# Adafruit_2_0_inch_240x320_IPS_TFT.net
KiCad netlist of a schematic drawn in EAGLE
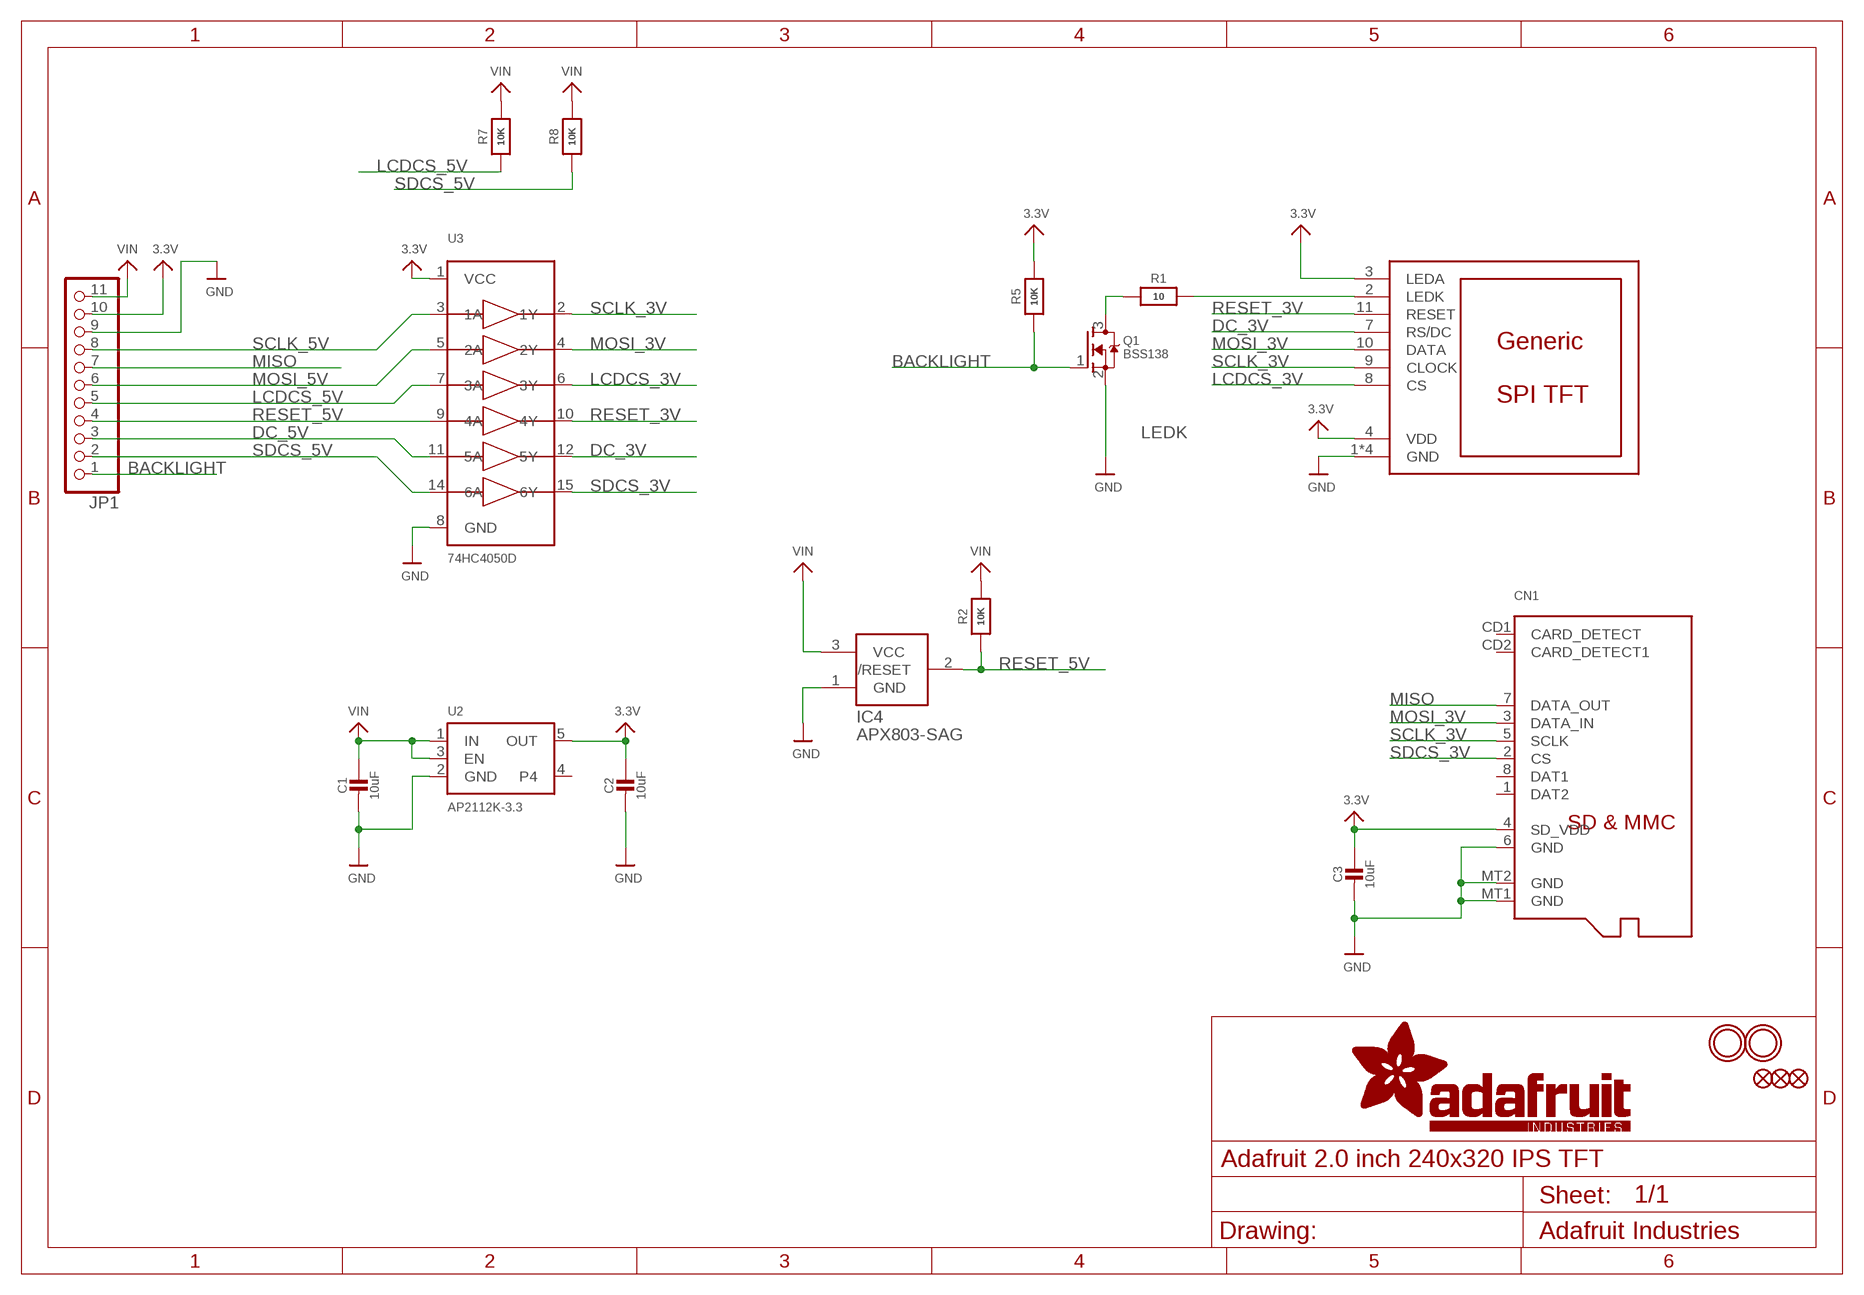
[diagram p0: schematic, sheet 1]

(export (version "E")
  (design (tool "Eeschema 10.0.6"))
  (components
    (comp (ref "C1")
      (value "10uF")
      (footprint "eagle-import:0805-NO")
      (libsource (lib "eagle-import") (part "CAP_CERAMIC0805-NOOUTLINE"))
    )
    (comp (ref "C2")
      (value "10uF")
      (footprint "eagle-import:0805-NO")
      (libsource (lib "eagle-import") (part "CAP_CERAMIC0805-NOOUTLINE"))
    )
    (comp (ref "C3")
      (value "10uF")
      (footprint "eagle-import:0805-NO")
      (libsource (lib "eagle-import") (part "CAP_CERAMIC0805-NOOUTLINE"))
    )
    (comp (ref "CN1")
      (value "MICROSD")
      (footprint "eagle-import:MICROSD")
      (libsource (lib "eagle-import") (part "MICROSD"))
    )
    (comp (ref "DISP1")
      (value "DISP_LCD_GENERIC_SPI_2.0IN_240X320")
      (footprint "eagle-import:TFT_2.0IN_240X320_12P")
      (libsource (lib "eagle-import") (part "DISP_LCD_GENERIC_SPI_2.0IN_240X320"))
    )
    (comp (ref "FID1")
      (value "FIDUCIAL_1MM")
      (footprint "eagle-import:FIDUCIAL_1MM")
      (libsource (lib "eagle-import") (part "FIDUCIAL_1MM"))
    )
    (comp (ref "FID2")
      (value "FIDUCIAL_1MM")
      (footprint "eagle-import:FIDUCIAL_1MM")
      (libsource (lib "eagle-import") (part "FIDUCIAL_1MM"))
    )
    (comp (ref "FID3")
      (value "FIDUCIAL_1MM")
      (footprint "eagle-import:FIDUCIAL_1MM")
      (fields (field (name "BOM") "EXCLUDE"))
      (libsource (lib "eagle-import") (part "FIDUCIAL_1MM"))
    )
    (comp (ref "IC4")
      (value "APX803-SAG")
      (footprint "eagle-import:SOT23")
      (libsource (lib "eagle-import") (part "AXP083-SAG"))
    )
    (comp (ref "JP1")
      (value "HEADER-1X1176MIL")
      (footprint "eagle-import:1X11_ROUND_76")
      (libsource (lib "eagle-import") (part "HEADER-1X1176MIL"))
    )
    (comp (ref "Q1")
      (value "BSS138")
      (footprint "eagle-import:SOT23-R")
      (libsource (lib "eagle-import") (part "MOSFET-NREFLOW"))
    )
    (comp (ref "R1")
      (value "10")
      (footprint "eagle-import:0805-NO")
      (libsource (lib "eagle-import") (part "RESISTOR0805_NOOUTLINE"))
    )
    (comp (ref "R2")
      (value "10K")
      (footprint "eagle-import:0805-NO")
      (libsource (lib "eagle-import") (part "RESISTOR0805_NOOUTLINE"))
    )
    (comp (ref "R5")
      (value "10K")
      (footprint "eagle-import:0805-NO")
      (libsource (lib "eagle-import") (part "RESISTOR0805_NOOUTLINE"))
    )
    (comp (ref "R7")
      (value "10K")
      (footprint "eagle-import:0805-NO")
      (libsource (lib "eagle-import") (part "RESISTOR0805_NOOUTLINE"))
    )
    (comp (ref "R8")
      (value "10K")
      (footprint "eagle-import:0805-NO")
      (libsource (lib "eagle-import") (part "RESISTOR0805_NOOUTLINE"))
    )
    (comp (ref "U$3")
      (value "MOUNTINGHOLE2.5")
      (footprint "eagle-import:MOUNTINGHOLE_2.5_PLATED")
      (libsource (lib "eagle-import") (part "MOUNTINGHOLE2.5"))
    )
    (comp (ref "U$4")
      (value "MOUNTINGHOLE2.5")
      (footprint "eagle-import:MOUNTINGHOLE_2.5_PLATED")
      (libsource (lib "eagle-import") (part "MOUNTINGHOLE2.5"))
    )
    (comp (ref "U2")
      (value "AP2112K-3.3")
      (footprint "eagle-import:SOT23-5")
      (libsource (lib "eagle-import") (part "VREG_SOT23-5"))
    )
    (comp (ref "U3")
      (value "74HC4050D")
      (footprint "eagle-import:SOIC16")
      (libsource (lib "eagle-import") (part "74HC4050D"))
    )
  )
  (nets
    (net (code "1") (name "/BACKLIGHT") (class "Default")
      (node (ref "JP1") (pin "1") (pinfunction "1_1") (pintype "passive"))
      (node (ref "Q1") (pin "1") (pinfunction "G_1") (pintype "bidirectional"))
      (node (ref "R5") (pin "1") (pinfunction "1_1") (pintype "passive"))
    )
    (net (code "2") (name "/DC_3V") (class "Default")
      (node (ref "DISP1") (pin "7") (pinfunction "RS/DC_7") (pintype "input"))
      (node (ref "U3") (pin "12") (pinfunction "5Y_12") (pintype "bidirectional"))
    )
    (net (code "3") (name "/DC_5V") (class "Default")
      (node (ref "JP1") (pin "3") (pinfunction "3_3") (pintype "passive"))
      (node (ref "U3") (pin "11") (pinfunction "5A_11") (pintype "bidirectional"))
    )
    (net (code "4") (name "/LCDCS_3V") (class "Default")
      (node (ref "DISP1") (pin "8") (pinfunction "CS_8") (pintype "input"))
      (node (ref "U3") (pin "6") (pinfunction "3Y_6") (pintype "bidirectional"))
    )
    (net (code "5") (name "/LCDCS_5V") (class "Default")
      (node (ref "JP1") (pin "5") (pinfunction "5_5") (pintype "passive"))
      (node (ref "R7") (pin "1") (pinfunction "1_1") (pintype "passive"))
      (node (ref "U3") (pin "7") (pinfunction "3A_7") (pintype "bidirectional"))
    )
    (net (code "6") (name "/LEDK") (class "Default")
      (node (ref "Q1") (pin "3") (pinfunction "D_3") (pintype "bidirectional"))
      (node (ref "R1") (pin "1") (pinfunction "1_1") (pintype "passive"))
    )
    (net (code "7") (name "/MISO") (class "Default")
      (node (ref "CN1") (pin "7") (pinfunction "DATA_OUT_7") (pintype "output"))
      (node (ref "JP1") (pin "7") (pinfunction "7_7") (pintype "passive"))
    )
    (net (code "8") (name "/MOSI_3V") (class "Default")
      (node (ref "CN1") (pin "3") (pinfunction "DATA_IN_3") (pintype "input"))
      (node (ref "DISP1") (pin "10") (pinfunction "DATA_10") (pintype "bidirectional"))
      (node (ref "U3") (pin "4") (pinfunction "2Y_4") (pintype "bidirectional"))
    )
    (net (code "9") (name "/MOSI_5V") (class "Default")
      (node (ref "JP1") (pin "6") (pinfunction "6_6") (pintype "passive"))
      (node (ref "U3") (pin "5") (pinfunction "2A_5") (pintype "bidirectional"))
    )
    (net (code "10") (name "/RESET_3V") (class "Default")
      (node (ref "DISP1") (pin "11") (pinfunction "RESET_11") (pintype "input"))
      (node (ref "U3") (pin "10") (pinfunction "4Y_10") (pintype "bidirectional"))
    )
    (net (code "11") (name "/RESET_5V") (class "Default")
      (node (ref "IC4") (pin "2") (pinfunction "/RESET_2") (pintype "output"))
      (node (ref "JP1") (pin "4") (pinfunction "4_4") (pintype "passive"))
      (node (ref "R2") (pin "1") (pinfunction "1_1") (pintype "passive"))
      (node (ref "U3") (pin "9") (pinfunction "4A_9") (pintype "bidirectional"))
    )
    (net (code "12") (name "/SCLK_3V") (class "Default")
      (node (ref "CN1") (pin "5") (pinfunction "SCLK_5") (pintype "input"))
      (node (ref "DISP1") (pin "9") (pinfunction "CLOCK_9") (pintype "input"))
      (node (ref "U3") (pin "2") (pinfunction "1Y_2") (pintype "bidirectional"))
    )
    (net (code "13") (name "/SCLK_5V") (class "Default")
      (node (ref "JP1") (pin "8") (pinfunction "8_8") (pintype "passive"))
      (node (ref "U3") (pin "3") (pinfunction "1A_3") (pintype "bidirectional"))
    )
    (net (code "14") (name "/SDCS_3V") (class "Default")
      (node (ref "CN1") (pin "2") (pinfunction "CS_2") (pintype "input"))
      (node (ref "U3") (pin "15") (pinfunction "6Y_15") (pintype "bidirectional"))
    )
    (net (code "15") (name "/SDCS_5V") (class "Default")
      (node (ref "JP1") (pin "2") (pinfunction "2_2") (pintype "passive"))
      (node (ref "R8") (pin "1") (pinfunction "1_1") (pintype "passive"))
      (node (ref "U3") (pin "14") (pinfunction "6A_14") (pintype "bidirectional"))
    )
    (net (code "16") (name "3.3V") (class "Default")
      (node (ref "C2") (pin "1") (pinfunction "1_1") (pintype "passive"))
      (node (ref "C3") (pin "1") (pinfunction "1_1") (pintype "passive"))
      (node (ref "CN1") (pin "4") (pinfunction "SD_VDD_4") (pintype "power_in"))
      (node (ref "DISP1") (pin "3") (pinfunction "LEDA_3") (pintype "input"))
      (node (ref "DISP1") (pin "4") (pinfunction "VDD_4") (pintype "power_in"))
      (node (ref "JP1") (pin "10") (pinfunction "10_10") (pintype "passive"))
      (node (ref "R5") (pin "2") (pinfunction "2_2") (pintype "passive"))
      (node (ref "U2") (pin "5") (pinfunction "OUT_5") (pintype "power_in"))
      (node (ref "U3") (pin "1") (pinfunction "VCC_1") (pintype "bidirectional"))
    )
    (net (code "17") (name "GND") (class "Default")
      (node (ref "C1") (pin "2") (pinfunction "2_2") (pintype "passive"))
      (node (ref "C2") (pin "2") (pinfunction "2_2") (pintype "passive"))
      (node (ref "C3") (pin "2") (pinfunction "2_2") (pintype "passive"))
      (node (ref "CN1") (pin "6") (pinfunction "GND_6") (pintype "power_in"))
      (node (ref "CN1") (pin "MT1") (pinfunction "GND_MT1") (pintype "power_in"))
      (node (ref "CN1") (pin "MT2") (pinfunction "GND_MT2") (pintype "power_in"))
      (node (ref "DISP1") (pin "1") (pinfunction "GND_1") (pintype "power_in"))
      (node (ref "DISP1") (pin "12") (pinfunction "GND_12") (pintype "power_in"))
      (node (ref "DISP1") (pin "5") (pinfunction "GND_5") (pintype "power_in"))
      (node (ref "DISP1") (pin "6") (pinfunction "GND_6") (pintype "power_in"))
      (node (ref "IC4") (pin "1") (pinfunction "GND_1") (pintype "power_in"))
      (node (ref "JP1") (pin "9") (pinfunction "9_9") (pintype "passive"))
      (node (ref "Q1") (pin "2") (pinfunction "S_2") (pintype "bidirectional"))
      (node (ref "U2") (pin "2") (pinfunction "GND_2") (pintype "power_in"))
      (node (ref "U3") (pin "8") (pinfunction "GND_8") (pintype "bidirectional"))
    )
    (net (code "18") (name "Net-(DISP1-LEDK)") (class "Default")
      (node (ref "DISP1") (pin "2") (pinfunction "LEDK_2") (pintype "input"))
      (node (ref "R1") (pin "2") (pinfunction "2_2") (pintype "passive"))
    )
    (net (code "19") (name "VIN") (class "Default")
      (node (ref "C1") (pin "1") (pinfunction "1_1") (pintype "passive"))
      (node (ref "IC4") (pin "3") (pinfunction "VCC_3") (pintype "power_in"))
      (node (ref "JP1") (pin "11") (pinfunction "11_11") (pintype "passive"))
      (node (ref "R2") (pin "2") (pinfunction "2_2") (pintype "passive"))
      (node (ref "R7") (pin "2") (pinfunction "2_2") (pintype "passive"))
      (node (ref "R8") (pin "2") (pinfunction "2_2") (pintype "passive"))
      (node (ref "U2") (pin "1") (pinfunction "IN_1") (pintype "power_in"))
      (node (ref "U2") (pin "3") (pinfunction "EN_3") (pintype "input"))
    )
    (net (code "20") (name "unconnected-(CN1-CARD_DETECT-PadCD1)") (class "Default")
      (node (ref "CN1") (pin "CD1") (pinfunction "CARD_DETECT_CD1") (pintype "passive"))
    )
    (net (code "21") (name "unconnected-(CN1-CARD_DETECT1-PadCD2)") (class "Default")
      (node (ref "CN1") (pin "CD2") (pinfunction "CARD_DETECT1_CD2") (pintype "passive"))
    )
    (net (code "22") (name "unconnected-(CN1-DAT1-Pad8)") (class "Default")
      (node (ref "CN1") (pin "8") (pinfunction "DAT1_8") (pintype "bidirectional"))
    )
    (net (code "23") (name "unconnected-(CN1-DAT2-Pad1)") (class "Default")
      (node (ref "CN1") (pin "1") (pinfunction "DAT2_1") (pintype "bidirectional"))
    )
    (net (code "24") (name "unconnected-(U2-P4-Pad4)") (class "Default")
      (node (ref "U2") (pin "4") (pinfunction "P4_4") (pintype "bidirectional"))
    )
  )
)
